# 9xVoice_MikeB_SMD_v1_0c.net
KiCad netlist of a schematic drawn in EAGLE
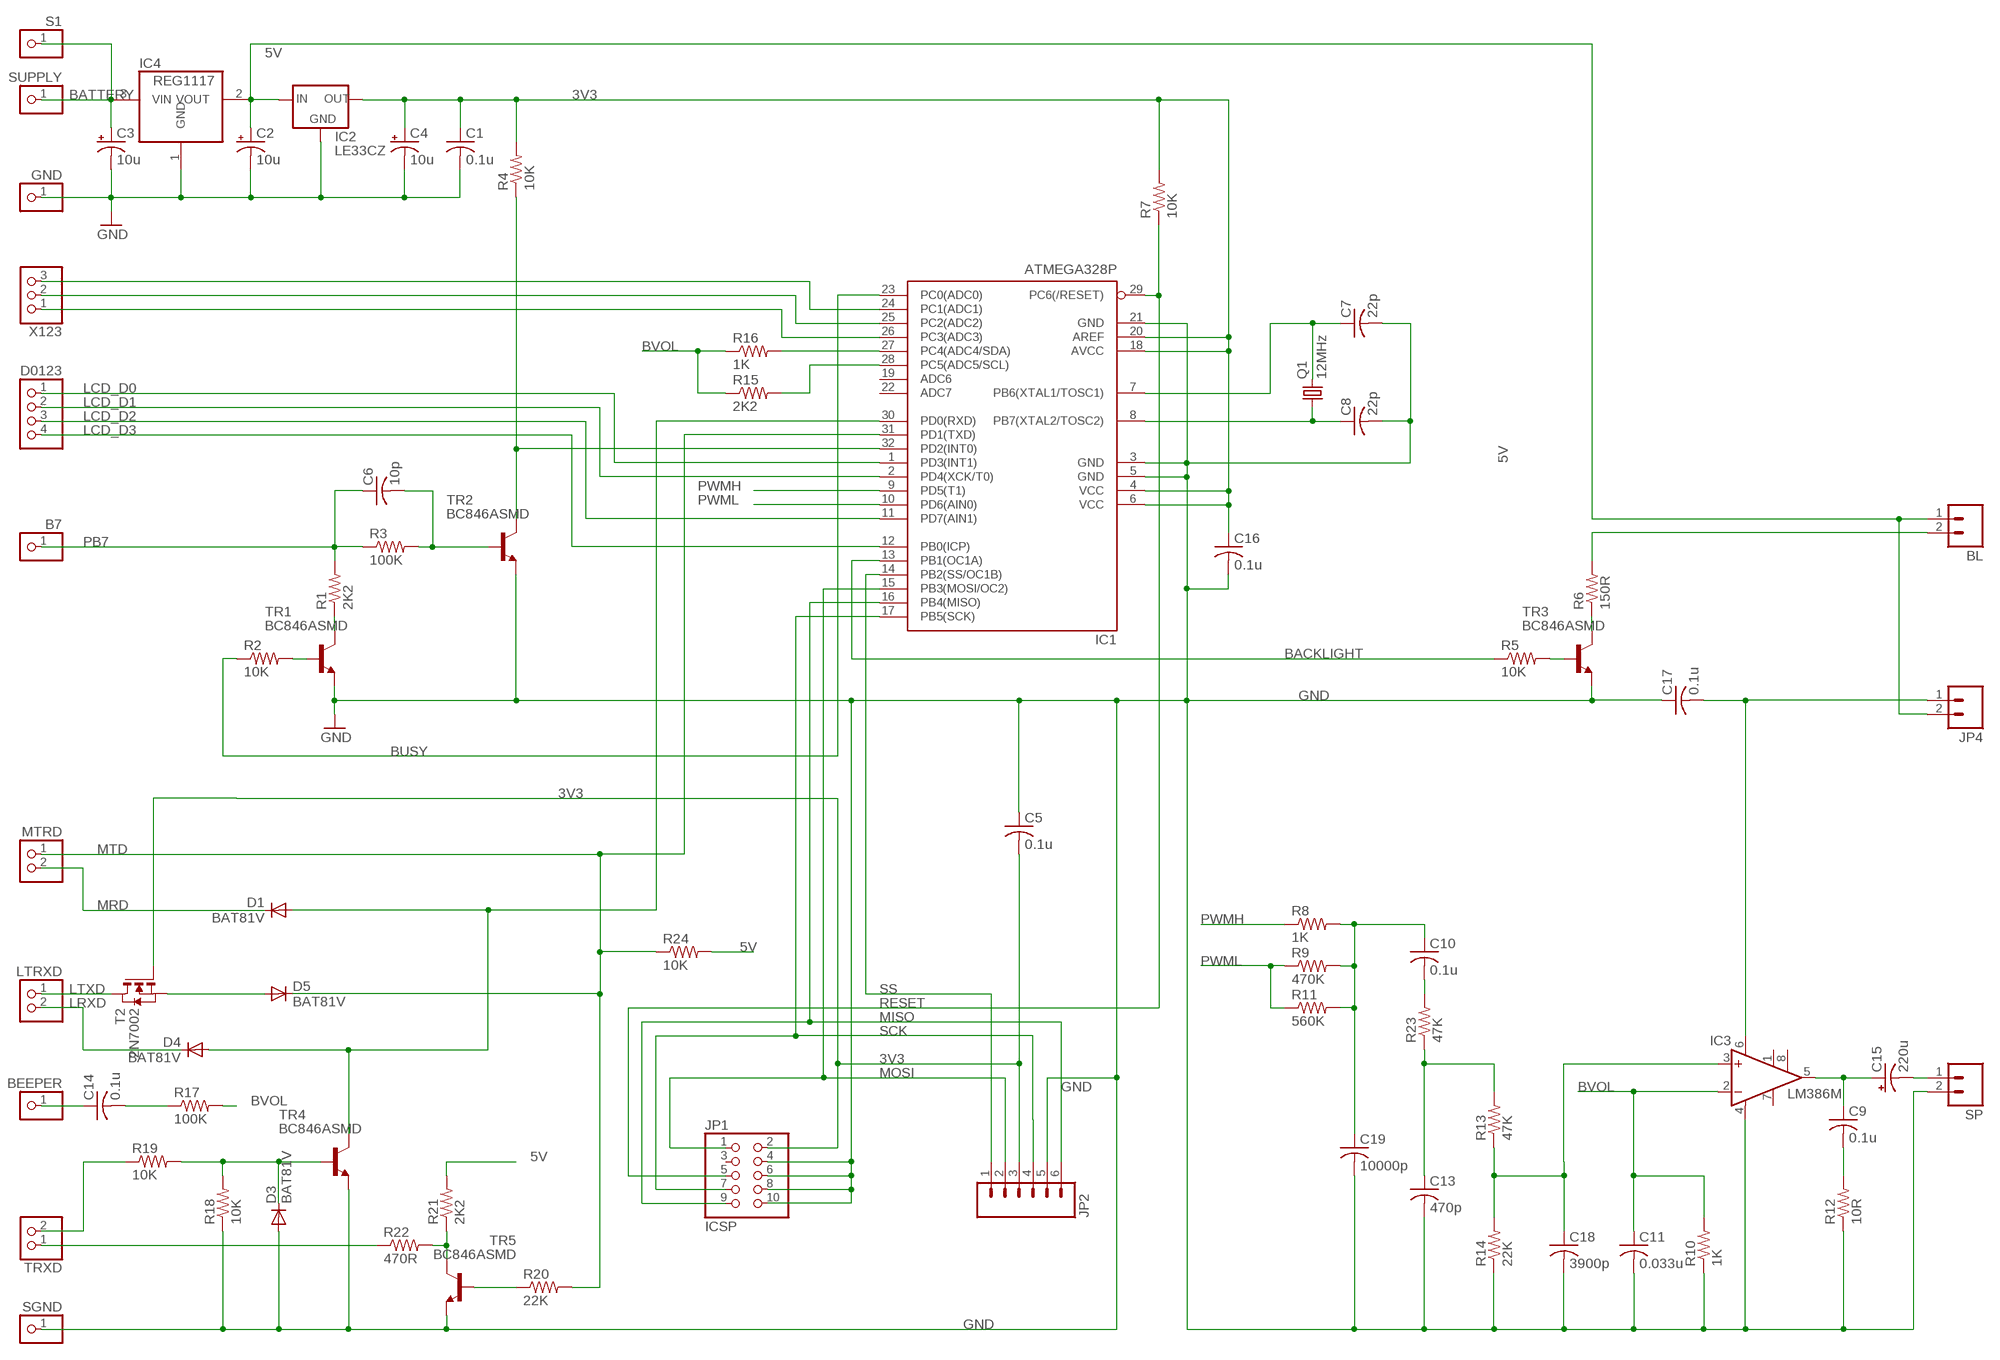
[diagram p0: schematic, sheet 1]

(export (version "E")
  (design (tool "Eeschema 10.0.6"))
  (components
    (comp (ref "B7")
      (value "PINHD-1X1")
      (footprint "eagle-import:1X01")
      (libsource (lib "eagle-import") (part "PINHD-1X1"))
    )
    (comp (ref "BEEPER")
      (value "PINHD-1X1")
      (footprint "eagle-import:1X01")
      (libsource (lib "eagle-import") (part "PINHD-1X1"))
    )
    (comp (ref "BL")
      (value "M02PTH")
      (footprint "eagle-import:1X02")
      (libsource (lib "eagle-import") (part "M02PTH"))
    )
    (comp (ref "C1")
      (value "0.1u")
      (footprint "eagle-import:C1206")
      (libsource (lib "eagle-import") (part "C-USC1206"))
    )
    (comp (ref "C2")
      (value "10u")
      (footprint "eagle-import:A_3216-18R")
      (libsource (lib "eagle-import") (part "CPOL-USA/3216-18R"))
    )
    (comp (ref "C3")
      (value "10u")
      (footprint "eagle-import:A_3216-18R")
      (libsource (lib "eagle-import") (part "CPOL-USA/3216-18R"))
    )
    (comp (ref "C4")
      (value "10u")
      (footprint "eagle-import:A_3216-18R")
      (libsource (lib "eagle-import") (part "CPOL-USA/3216-18R"))
    )
    (comp (ref "C5")
      (value "0.1u")
      (footprint "eagle-import:C1206")
      (libsource (lib "eagle-import") (part "C-USC1206"))
    )
    (comp (ref "C6")
      (value "10p")
      (footprint "eagle-import:C1206")
      (libsource (lib "eagle-import") (part "C-USC1206"))
    )
    (comp (ref "C7")
      (value "22p")
      (footprint "eagle-import:C1206")
      (libsource (lib "eagle-import") (part "C-USC1206"))
    )
    (comp (ref "C8")
      (value "22p")
      (footprint "eagle-import:C1206")
      (libsource (lib "eagle-import") (part "C-USC1206"))
    )
    (comp (ref "C9")
      (value "0.1u")
      (footprint "eagle-import:C1206")
      (libsource (lib "eagle-import") (part "C-USC1206"))
    )
    (comp (ref "C10")
      (value "0.1u")
      (footprint "eagle-import:C1206")
      (libsource (lib "eagle-import") (part "C-USC1206"))
    )
    (comp (ref "C11")
      (value "0.033u")
      (footprint "eagle-import:C1206")
      (libsource (lib "eagle-import") (part "C-USC1206"))
    )
    (comp (ref "C13")
      (value "470p")
      (footprint "eagle-import:C1206")
      (libsource (lib "eagle-import") (part "C-USC1206"))
    )
    (comp (ref "C14")
      (value "0.1u")
      (footprint "eagle-import:C1206")
      (libsource (lib "eagle-import") (part "C-USC1206"))
    )
    (comp (ref "C15")
      (value "220u")
      (footprint "eagle-import:CT7343")
      (libsource (lib "eagle-import") (part "CPOL-USCT7343"))
    )
    (comp (ref "C16")
      (value "0.1u")
      (footprint "eagle-import:C1206")
      (libsource (lib "eagle-import") (part "C-USC1206"))
    )
    (comp (ref "C17")
      (value "0.1u")
      (footprint "eagle-import:C1206")
      (libsource (lib "eagle-import") (part "C-USC1206"))
    )
    (comp (ref "C18")
      (value "3900p")
      (footprint "eagle-import:C1206")
      (libsource (lib "eagle-import") (part "C-USC1206"))
    )
    (comp (ref "C19")
      (value "10000p")
      (footprint "eagle-import:C1206")
      (libsource (lib "eagle-import") (part "C-USC1206"))
    )
    (comp (ref "D1")
      (value "BAT81V")
      (footprint "eagle-import:SOD123")
      (libsource (lib "eagle-import") (part "DIODE-SOD123"))
    )
    (comp (ref "D3")
      (value "BAT81V")
      (footprint "eagle-import:SOD123")
      (libsource (lib "eagle-import") (part "DIODE-SOD123"))
    )
    (comp (ref "D4")
      (value "BAT81V")
      (footprint "eagle-import:SOD123")
      (libsource (lib "eagle-import") (part "DIODE-SOD123"))
    )
    (comp (ref "D5")
      (value "BAT81V")
      (footprint "eagle-import:SOD123")
      (libsource (lib "eagle-import") (part "DIODE-SOD123"))
    )
    (comp (ref "D0123")
      (value "PINHD-1X4")
      (footprint "eagle-import:1X04")
      (libsource (lib "eagle-import") (part "PINHD-1X4"))
    )
    (comp (ref "GND")
      (value "PINHD-1X1")
      (footprint "eagle-import:1X01")
      (libsource (lib "eagle-import") (part "PINHD-1X1"))
    )
    (comp (ref "IC1")
      (value "ATMEGA328P")
      (footprint "eagle-import:TQFP32-08")
      (fields
        (field (name "MPN") "ATMEGA8-16AU")
        (field (name "MPN_1") "ATMEGA8-16AU")
        (field (name "OC_FARNELL") "9171371")
        (field (name "OC_NEWARK") "73M8863")
      )
      (libsource (lib "eagle-import") (part "MEGA8-AI"))
    )
    (comp (ref "IC2")
      (value "LE33CZ")
      (footprint "eagle-import:SOT23")
      (libsource (lib "eagle-import") (part "XC63FPM"))
    )
    (comp (ref "IC3")
      (value "LM386M")
      (footprint "eagle-import:SO08")
      (libsource (lib "eagle-import") (part "LM386?-M1"))
    )
    (comp (ref "IC4")
      (value "REG1117")
      (footprint "eagle-import:SOT223")
      (libsource (lib "eagle-import") (part "REG1117"))
    )
    (comp (ref "JP1")
      (value "ICSP")
      (footprint "eagle-import:2X05")
      (libsource (lib "eagle-import") (part "PINHD-2X5"))
    )
    (comp (ref "JP2")
      (value "M06SIP")
      (footprint "eagle-import:1X06")
      (libsource (lib "eagle-import") (part "M06SIP"))
    )
    (comp (ref "JP4")
      (value "M02PTH")
      (footprint "eagle-import:1X02")
      (libsource (lib "eagle-import") (part "M02PTH"))
    )
    (comp (ref "LTRXD")
      (value "PINHD-1X2")
      (footprint "eagle-import:1X02")
      (libsource (lib "eagle-import") (part "PINHD-1X2"))
    )
    (comp (ref "MTRD")
      (value "PINHD-1X2")
      (footprint "eagle-import:1X02")
      (libsource (lib "eagle-import") (part "PINHD-1X2"))
    )
    (comp (ref "Q1")
      (value "12MHz")
      (footprint "eagle-import:2-SMD")
      (libsource (lib "eagle-import") (part "7A"))
    )
    (comp (ref "R1")
      (value "2K2")
      (footprint "eagle-import:R1206")
      (libsource (lib "eagle-import") (part "R-US_R1206"))
    )
    (comp (ref "R2")
      (value "10K")
      (footprint "eagle-import:R1206")
      (libsource (lib "eagle-import") (part "R-US_R1206"))
    )
    (comp (ref "R3")
      (value "100K")
      (footprint "eagle-import:R1206")
      (libsource (lib "eagle-import") (part "R-US_R1206"))
    )
    (comp (ref "R4")
      (value "10K")
      (footprint "eagle-import:R1206")
      (libsource (lib "eagle-import") (part "R-US_R1206"))
    )
    (comp (ref "R5")
      (value "10K")
      (footprint "eagle-import:R1206")
      (libsource (lib "eagle-import") (part "R-US_R1206"))
    )
    (comp (ref "R6")
      (value "150R")
      (footprint "eagle-import:R1206")
      (libsource (lib "eagle-import") (part "R-US_R1206"))
    )
    (comp (ref "R7")
      (value "10K")
      (footprint "eagle-import:R1206")
      (libsource (lib "eagle-import") (part "R-US_R1206"))
    )
    (comp (ref "R8")
      (value "1K")
      (footprint "eagle-import:R1206")
      (libsource (lib "eagle-import") (part "R-US_R1206"))
    )
    (comp (ref "R9")
      (value "470K")
      (footprint "eagle-import:R1206")
      (libsource (lib "eagle-import") (part "R-US_R1206"))
    )
    (comp (ref "R10")
      (value "1K")
      (footprint "eagle-import:R1206")
      (libsource (lib "eagle-import") (part "R-US_R1206"))
    )
    (comp (ref "R11")
      (value "560K")
      (footprint "eagle-import:R1206")
      (libsource (lib "eagle-import") (part "R-US_R1206"))
    )
    (comp (ref "R12")
      (value "10R")
      (footprint "eagle-import:R1206")
      (libsource (lib "eagle-import") (part "R-US_R1206"))
    )
    (comp (ref "R13")
      (value "47K")
      (footprint "eagle-import:R1206")
      (libsource (lib "eagle-import") (part "R-US_R1206"))
    )
    (comp (ref "R14")
      (value "22K")
      (footprint "eagle-import:R1206")
      (libsource (lib "eagle-import") (part "R-US_R1206"))
    )
    (comp (ref "R15")
      (value "2K2")
      (footprint "eagle-import:R1206")
      (libsource (lib "eagle-import") (part "R-US_R1206"))
    )
    (comp (ref "R16")
      (value "1K")
      (footprint "eagle-import:R1206")
      (libsource (lib "eagle-import") (part "R-US_R1206"))
    )
    (comp (ref "R17")
      (value "100K")
      (footprint "eagle-import:R1206")
      (libsource (lib "eagle-import") (part "R-US_R1206"))
    )
    (comp (ref "R18")
      (value "10K")
      (footprint "eagle-import:R1206")
      (libsource (lib "eagle-import") (part "R-US_R1206"))
    )
    (comp (ref "R19")
      (value "10K")
      (footprint "eagle-import:R1206")
      (libsource (lib "eagle-import") (part "R-US_R1206"))
    )
    (comp (ref "R20")
      (value "22K")
      (footprint "eagle-import:R1206")
      (libsource (lib "eagle-import") (part "R-US_R1206"))
    )
    (comp (ref "R21")
      (value "2K2")
      (footprint "eagle-import:R1206")
      (libsource (lib "eagle-import") (part "R-US_R1206"))
    )
    (comp (ref "R22")
      (value "470R")
      (footprint "eagle-import:R1206")
      (libsource (lib "eagle-import") (part "R-US_R1206"))
    )
    (comp (ref "R23")
      (value "47K")
      (footprint "eagle-import:R1206")
      (libsource (lib "eagle-import") (part "R-US_R1206"))
    )
    (comp (ref "R24")
      (value "10K")
      (footprint "eagle-import:R1206")
      (libsource (lib "eagle-import") (part "R-US_R1206"))
    )
    (comp (ref "S1")
      (value "PINHD-1X1")
      (footprint "eagle-import:1X01")
      (libsource (lib "eagle-import") (part "PINHD-1X1"))
    )
    (comp (ref "SGND")
      (value "PINHD-1X1")
      (footprint "eagle-import:1X01")
      (libsource (lib "eagle-import") (part "PINHD-1X1"))
    )
    (comp (ref "SP")
      (value "M02PTH")
      (footprint "eagle-import:1X02")
      (libsource (lib "eagle-import") (part "M02PTH"))
    )
    (comp (ref "SUPPLY")
      (value "PINHD-1X1")
      (footprint "eagle-import:1X01")
      (libsource (lib "eagle-import") (part "PINHD-1X1"))
    )
    (comp (ref "T2")
      (value "2N7002")
      (footprint "eagle-import:SOT-23")
      (libsource (lib "eagle-import") (part "NMOSSOT23"))
    )
    (comp (ref "TR1")
      (value "BC846ASMD")
      (footprint "eagle-import:SOT23")
      (libsource (lib "eagle-import") (part "BC846SMDA"))
    )
    (comp (ref "TR2")
      (value "BC846ASMD")
      (footprint "eagle-import:SOT23")
      (libsource (lib "eagle-import") (part "BC846SMDA"))
    )
    (comp (ref "TR3")
      (value "BC846ASMD")
      (footprint "eagle-import:SOT23")
      (libsource (lib "eagle-import") (part "BC846SMDA"))
    )
    (comp (ref "TR4")
      (value "BC846ASMD")
      (footprint "eagle-import:SOT23")
      (libsource (lib "eagle-import") (part "BC846SMDA"))
    )
    (comp (ref "TR5")
      (value "BC846ASMD")
      (footprint "eagle-import:SOT23")
      (libsource (lib "eagle-import") (part "transistor-npn_BC846SMDA"))
    )
    (comp (ref "TRXD")
      (value "PINHD-1X2")
      (footprint "eagle-import:1X02")
      (libsource (lib "eagle-import") (part "PINHD-1X2"))
    )
    (comp (ref "X123")
      (value "PINHD-1X3")
      (footprint "eagle-import:1X03")
      (libsource (lib "eagle-import") (part "PINHD-1X3"))
    )
  )
  (nets
    (net (code "1") (name "/3V3") (class "Default")
      (node (ref "C1") (pin "1") (pinfunction "1_1") (pintype "passive"))
      (node (ref "C16") (pin "1") (pinfunction "1_1") (pintype "passive"))
      (node (ref "C4") (pin "+") (pinfunction "+_+") (pintype "passive"))
      (node (ref "C5") (pin "2") (pinfunction "2_2") (pintype "passive"))
      (node (ref "IC1") (pin "18") (pinfunction "AVCC_18") (pintype "power_in"))
      (node (ref "IC1") (pin "20") (pinfunction "AREF_20") (pintype "passive"))
      (node (ref "IC1") (pin "4") (pinfunction "VCC_4") (pintype "power_in"))
      (node (ref "IC1") (pin "6") (pinfunction "VCC_6") (pintype "power_in"))
      (node (ref "IC2") (pin "2") (pinfunction "OUT_2") (pintype "passive"))
      (node (ref "JP1") (pin "2") (pinfunction "2_2") (pintype "passive"))
      (node (ref "JP2") (pin "3") (pinfunction "3_3") (pintype "passive"))
      (node (ref "R4") (pin "2") (pinfunction "2_2") (pintype "passive"))
      (node (ref "R7") (pin "2") (pinfunction "2_2") (pintype "passive"))
      (node (ref "T2") (pin "3") (pinfunction "G_3") (pintype "passive"))
    )
    (net (code "2") (name "/5V") (class "Default")
      (node (ref "BL") (pin "1") (pinfunction "1_1") (pintype "passive"))
      (node (ref "C2") (pin "+") (pinfunction "+_+") (pintype "passive"))
      (node (ref "IC2") (pin "3") (pinfunction "IN_3") (pintype "input"))
      (node (ref "IC4") (pin "2") (pinfunction "VOUT_2") (pintype "output"))
      (node (ref "JP4") (pin "2") (pinfunction "2_2") (pintype "passive"))
      (node (ref "R21") (pin "2") (pinfunction "2_2") (pintype "passive"))
      (node (ref "R24") (pin "2") (pinfunction "2_2") (pintype "passive"))
    )
    (net (code "3") (name "/BACKLIGHT") (class "Default")
      (node (ref "IC1") (pin "13") (pinfunction "PB1(OC1A)_13") (pintype "bidirectional"))
      (node (ref "R5") (pin "1") (pinfunction "1_1") (pintype "passive"))
    )
    (net (code "4") (name "/BATTERY") (class "Default")
      (node (ref "C3") (pin "+") (pinfunction "+_+") (pintype "passive"))
      (node (ref "IC4") (pin "3") (pinfunction "VIN_3") (pintype "input"))
      (node (ref "S1") (pin "1") (pinfunction "1_1") (pintype "passive"))
      (node (ref "SUPPLY") (pin "1") (pinfunction "1_1") (pintype "passive"))
    )
    (net (code "5") (name "/BUSY") (class "Default")
      (node (ref "IC1") (pin "23") (pinfunction "PC0(ADC0)_23") (pintype "bidirectional"))
      (node (ref "R2") (pin "1") (pinfunction "1_1") (pintype "passive"))
    )
    (net (code "6") (name "/BVOL") (class "Default")
      (node (ref "C11") (pin "1") (pinfunction "1_1") (pintype "passive"))
      (node (ref "IC3") (pin "2") (pinfunction "-IN_2") (pintype "input"))
      (node (ref "R10") (pin "2") (pinfunction "2_2") (pintype "passive"))
      (node (ref "R15") (pin "1") (pinfunction "1_1") (pintype "passive"))
      (node (ref "R16") (pin "1") (pinfunction "1_1") (pintype "passive"))
      (node (ref "R17") (pin "2") (pinfunction "2_2") (pintype "passive"))
    )
    (net (code "7") (name "/LCD_D0") (class "Default")
      (node (ref "D0123") (pin "1") (pinfunction "1_1") (pintype "passive"))
      (node (ref "IC1") (pin "1") (pinfunction "PD3(INT1)_1") (pintype "bidirectional"))
    )
    (net (code "8") (name "/LCD_D1") (class "Default")
      (node (ref "D0123") (pin "2") (pinfunction "2_2") (pintype "passive"))
      (node (ref "IC1") (pin "2") (pinfunction "PD4(XCK/T0)_2") (pintype "bidirectional"))
    )
    (net (code "9") (name "/LCD_D2") (class "Default")
      (node (ref "D0123") (pin "3") (pinfunction "3_3") (pintype "passive"))
      (node (ref "IC1") (pin "11") (pinfunction "PD7(AIN1)_11") (pintype "bidirectional"))
    )
    (net (code "10") (name "/LCD_D3") (class "Default")
      (node (ref "D0123") (pin "4") (pinfunction "4_4") (pintype "passive"))
      (node (ref "IC1") (pin "12") (pinfunction "PB0(ICP)_12") (pintype "bidirectional"))
    )
    (net (code "11") (name "/LRXD") (class "Default")
      (node (ref "D4") (pin "C") (pinfunction "C_C") (pintype "passive"))
      (node (ref "LTRXD") (pin "2") (pinfunction "2_2") (pintype "passive"))
    )
    (net (code "12") (name "/LTXD") (class "Default")
      (node (ref "LTRXD") (pin "1") (pinfunction "1_1") (pintype "passive"))
      (node (ref "T2") (pin "1") (pinfunction "D_1") (pintype "passive"))
    )
    (net (code "13") (name "/MISO") (class "Default")
      (node (ref "IC1") (pin "16") (pinfunction "PB4(MISO)_16") (pintype "bidirectional"))
      (node (ref "JP1") (pin "9") (pinfunction "9_9") (pintype "passive"))
      (node (ref "JP2") (pin "6") (pinfunction "6_6") (pintype "passive"))
    )
    (net (code "14") (name "/MOSI") (class "Default")
      (node (ref "IC1") (pin "15") (pinfunction "PB3(MOSI/OC2)_15") (pintype "bidirectional"))
      (node (ref "JP1") (pin "1") (pinfunction "1_1") (pintype "passive"))
      (node (ref "JP2") (pin "2") (pinfunction "2_2") (pintype "passive"))
    )
    (net (code "15") (name "/MRD") (class "Default")
      (node (ref "D1") (pin "C") (pinfunction "C_C") (pintype "passive"))
      (node (ref "MTRD") (pin "2") (pinfunction "2_2") (pintype "passive"))
    )
    (net (code "16") (name "/MTD") (class "Default")
      (node (ref "D5") (pin "C") (pinfunction "C_C") (pintype "passive"))
      (node (ref "IC1") (pin "31") (pinfunction "PD1(TXD)_31") (pintype "bidirectional"))
      (node (ref "MTRD") (pin "1") (pinfunction "1_1") (pintype "passive"))
      (node (ref "R20") (pin "2") (pinfunction "2_2") (pintype "passive"))
      (node (ref "R24") (pin "1") (pinfunction "1_1") (pintype "passive"))
    )
    (net (code "17") (name "/PB7") (class "Default")
      (node (ref "B7") (pin "1") (pinfunction "1_1") (pintype "passive"))
      (node (ref "C6") (pin "1") (pinfunction "1_1") (pintype "passive"))
      (node (ref "R1") (pin "2") (pinfunction "2_2") (pintype "passive"))
      (node (ref "R3") (pin "1") (pinfunction "1_1") (pintype "passive"))
    )
    (net (code "18") (name "/PWMH") (class "Default")
      (node (ref "IC1") (pin "9") (pinfunction "PD5(T1)_9") (pintype "bidirectional"))
      (node (ref "R8") (pin "1") (pinfunction "1_1") (pintype "passive"))
    )
    (net (code "19") (name "/PWML") (class "Default")
      (node (ref "IC1") (pin "10") (pinfunction "PD6(AIN0)_10") (pintype "bidirectional"))
      (node (ref "R11") (pin "1") (pinfunction "1_1") (pintype "passive"))
      (node (ref "R9") (pin "1") (pinfunction "1_1") (pintype "passive"))
    )
    (net (code "20") (name "/RESET") (class "Default")
      (node (ref "IC1") (pin "29") (pinfunction "PC6(/RESET)_29") (pintype "bidirectional"))
      (node (ref "JP1") (pin "5") (pinfunction "5_5") (pintype "passive"))
      (node (ref "R7") (pin "1") (pinfunction "1_1") (pintype "passive"))
    )
    (net (code "21") (name "/SCK") (class "Default")
      (node (ref "IC1") (pin "17") (pinfunction "PB5(SCK)_17") (pintype "bidirectional"))
      (node (ref "JP1") (pin "7") (pinfunction "7_7") (pintype "passive"))
      (node (ref "JP2") (pin "4") (pinfunction "4_4") (pintype "passive"))
    )
    (net (code "22") (name "/SS") (class "Default")
      (node (ref "IC1") (pin "14") (pinfunction "PB2(SS/OC1B)_14") (pintype "bidirectional"))
      (node (ref "JP2") (pin "1") (pinfunction "1_1") (pintype "passive"))
    )
    (net (code "23") (name "GND") (class "Default")
      (node (ref "C1") (pin "2") (pinfunction "2_2") (pintype "passive"))
      (node (ref "C11") (pin "2") (pinfunction "2_2") (pintype "passive"))
      (node (ref "C13") (pin "2") (pinfunction "2_2") (pintype "passive"))
      (node (ref "C16") (pin "2") (pinfunction "2_2") (pintype "passive"))
      (node (ref "C17") (pin "1") (pinfunction "1_1") (pintype "passive"))
      (node (ref "C18") (pin "2") (pinfunction "2_2") (pintype "passive"))
      (node (ref "C19") (pin "2") (pinfunction "2_2") (pintype "passive"))
      (node (ref "C2") (pin "-") (pinfunction "-_-") (pintype "passive"))
      (node (ref "C3") (pin "-") (pinfunction "-_-") (pintype "passive"))
      (node (ref "C4") (pin "-") (pinfunction "-_-") (pintype "passive"))
      (node (ref "C5") (pin "1") (pinfunction "1_1") (pintype "passive"))
      (node (ref "C7") (pin "2") (pinfunction "2_2") (pintype "passive"))
      (node (ref "C8") (pin "2") (pinfunction "2_2") (pintype "passive"))
      (node (ref "D3") (pin "A") (pinfunction "A_A") (pintype "passive"))
      (node (ref "GND") (pin "1") (pinfunction "1_1") (pintype "passive"))
      (node (ref "IC1") (pin "21") (pinfunction "GND_21") (pintype "power_in"))
      (node (ref "IC1") (pin "3") (pinfunction "GND_3") (pintype "power_in"))
      (node (ref "IC1") (pin "5") (pinfunction "GND_5") (pintype "power_in"))
      (node (ref "IC2") (pin "1") (pinfunction "GND_1") (pintype "input"))
      (node (ref "IC3") (pin "4") (pinfunction "GND_4") (pintype "power_in"))
      (node (ref "IC4") (pin "1") (pinfunction "GND_1") (pintype "power_in"))
      (node (ref "JP1") (pin "10") (pinfunction "10_10") (pintype "passive"))
      (node (ref "JP1") (pin "4") (pinfunction "4_4") (pintype "passive"))
      (node (ref "JP1") (pin "6") (pinfunction "6_6") (pintype "passive"))
      (node (ref "JP1") (pin "8") (pinfunction "8_8") (pintype "passive"))
      (node (ref "JP2") (pin "5") (pinfunction "5_5") (pintype "passive"))
      (node (ref "R10") (pin "1") (pinfunction "1_1") (pintype "passive"))
      (node (ref "R12") (pin "1") (pinfunction "1_1") (pintype "passive"))
      (node (ref "R14") (pin "1") (pinfunction "1_1") (pintype "passive"))
      (node (ref "R18") (pin "1") (pinfunction "1_1") (pintype "passive"))
      (node (ref "SGND") (pin "1") (pinfunction "1_1") (pintype "passive"))
      (node (ref "SP") (pin "2") (pinfunction "2_2") (pintype "passive"))
      (node (ref "TR1") (pin "2") (pinfunction "E_2") (pintype "passive"))
      (node (ref "TR2") (pin "2") (pinfunction "E_2") (pintype "passive"))
      (node (ref "TR3") (pin "2") (pinfunction "E_2") (pintype "passive"))
      (node (ref "TR4") (pin "2") (pinfunction "E_2") (pintype "passive"))
      (node (ref "TR5") (pin "2") (pinfunction "E_2") (pintype "passive"))
    )
    (net (code "24") (name "Net-(BEEPER-Pad1)") (class "Default")
      (node (ref "BEEPER") (pin "1") (pinfunction "1_1") (pintype "passive"))
      (node (ref "C14") (pin "1") (pinfunction "1_1") (pintype "passive"))
    )
    (net (code "25") (name "Net-(BL-Pad2)") (class "Default")
      (node (ref "BL") (pin "2") (pinfunction "2_2") (pintype "passive"))
      (node (ref "R6") (pin "2") (pinfunction "2_2") (pintype "passive"))
    )
    (net (code "26") (name "Net-(C9-Pad2)") (class "Default")
      (node (ref "C9") (pin "2") (pinfunction "2_2") (pintype "passive"))
      (node (ref "R12") (pin "2") (pinfunction "2_2") (pintype "passive"))
    )
    (net (code "27") (name "Net-(C10-Pad1)") (class "Default")
      (node (ref "C10") (pin "1") (pinfunction "1_1") (pintype "passive"))
      (node (ref "C19") (pin "1") (pinfunction "1_1") (pintype "passive"))
      (node (ref "R11") (pin "2") (pinfunction "2_2") (pintype "passive"))
      (node (ref "R8") (pin "2") (pinfunction "2_2") (pintype "passive"))
      (node (ref "R9") (pin "2") (pinfunction "2_2") (pintype "passive"))
    )
    (net (code "28") (name "Net-(C10-Pad2)") (class "Default")
      (node (ref "C10") (pin "2") (pinfunction "2_2") (pintype "passive"))
      (node (ref "R23") (pin "2") (pinfunction "2_2") (pintype "passive"))
    )
    (net (code "29") (name "Net-(C13-Pad1)") (class "Default")
      (node (ref "C13") (pin "1") (pinfunction "1_1") (pintype "passive"))
      (node (ref "R13") (pin "2") (pinfunction "2_2") (pintype "passive"))
      (node (ref "R23") (pin "1") (pinfunction "1_1") (pintype "passive"))
    )
    (net (code "30") (name "Net-(C14-Pad2)") (class "Default")
      (node (ref "C14") (pin "2") (pinfunction "2_2") (pintype "passive"))
      (node (ref "R17") (pin "1") (pinfunction "1_1") (pintype "passive"))
    )
    (net (code "31") (name "Net-(C15-Pad-)") (class "Default")
      (node (ref "C15") (pin "-") (pinfunction "-_-") (pintype "passive"))
      (node (ref "SP") (pin "1") (pinfunction "1_1") (pintype "passive"))
    )
    (net (code "32") (name "Net-(IC1-PB6(XTAL1{slash}TOSC1))") (class "Default")
      (node (ref "C7") (pin "1") (pinfunction "1_1") (pintype "passive"))
      (node (ref "IC1") (pin "7") (pinfunction "PB6(XTAL1/TOSC1)_7") (pintype "bidirectional"))
      (node (ref "Q1") (pin "P$2") (pinfunction "2_P$2") (pintype "passive"))
    )
    (net (code "33") (name "Net-(IC1-PB7(XTAL2{slash}TOSC2))") (class "Default")
      (node (ref "C8") (pin "1") (pinfunction "1_1") (pintype "passive"))
      (node (ref "IC1") (pin "8") (pinfunction "PB7(XTAL2/TOSC2)_8") (pintype "bidirectional"))
      (node (ref "Q1") (pin "P$1") (pinfunction "1_P$1") (pintype "passive"))
    )
    (net (code "34") (name "Net-(IC1-PC1(ADC1))") (class "Default")
      (node (ref "IC1") (pin "24") (pinfunction "PC1(ADC1)_24") (pintype "bidirectional"))
      (node (ref "X123") (pin "3") (pinfunction "3_3") (pintype "passive"))
    )
    (net (code "35") (name "Net-(IC1-PC2(ADC2))") (class "Default")
      (node (ref "IC1") (pin "25") (pinfunction "PC2(ADC2)_25") (pintype "bidirectional"))
      (node (ref "X123") (pin "2") (pinfunction "2_2") (pintype "passive"))
    )
    (net (code "36") (name "Net-(IC1-PC3(ADC3))") (class "Default")
      (node (ref "IC1") (pin "26") (pinfunction "PC3(ADC3)_26") (pintype "bidirectional"))
      (node (ref "X123") (pin "1") (pinfunction "1_1") (pintype "passive"))
    )
    (net (code "37") (name "Net-(IC1-PC4(ADC4{slash}SDA))") (class "Default")
      (node (ref "IC1") (pin "27") (pinfunction "PC4(ADC4/SDA)_27") (pintype "bidirectional"))
      (node (ref "R16") (pin "2") (pinfunction "2_2") (pintype "passive"))
    )
    (net (code "38") (name "Net-(IC1-PC5(ADC5{slash}SCL))") (class "Default")
      (node (ref "IC1") (pin "28") (pinfunction "PC5(ADC5/SCL)_28") (pintype "bidirectional"))
      (node (ref "R15") (pin "2") (pinfunction "2_2") (pintype "passive"))
    )
    (net (code "39") (name "Net-(IC1-PD0(RXD))") (class "Default")
      (node (ref "D1") (pin "A") (pinfunction "A_A") (pintype "passive"))
      (node (ref "D4") (pin "A") (pinfunction "A_A") (pintype "passive"))
      (node (ref "IC1") (pin "30") (pinfunction "PD0(RXD)_30") (pintype "bidirectional"))
      (node (ref "TR4") (pin "3") (pinfunction "C_3") (pintype "passive"))
    )
    (net (code "40") (name "Net-(IC1-PD2(INT0))") (class "Default")
      (node (ref "IC1") (pin "32") (pinfunction "PD2(INT0)_32") (pintype "bidirectional"))
      (node (ref "R4") (pin "1") (pinfunction "1_1") (pintype "passive"))
      (node (ref "TR2") (pin "3") (pinfunction "C_3") (pintype "passive"))
    )
    (net (code "41") (name "Net-(IC3-+IN)") (class "Default")
      (node (ref "C18") (pin "1") (pinfunction "1_1") (pintype "passive"))
      (node (ref "IC3") (pin "3") (pinfunction "+IN_3") (pintype "input"))
      (node (ref "R13") (pin "1") (pinfunction "1_1") (pintype "passive"))
      (node (ref "R14") (pin "2") (pinfunction "2_2") (pintype "passive"))
    )
    (net (code "42") (name "Net-(IC3-OUT)") (class "Default")
      (node (ref "C15") (pin "+") (pinfunction "+_+") (pintype "passive"))
      (node (ref "C9") (pin "1") (pinfunction "1_1") (pintype "passive"))
      (node (ref "IC3") (pin "5") (pinfunction "OUT_5") (pintype "output"))
    )
    (net (code "43") (name "Net-(IC3-VS)") (class "Default")
      (node (ref "C17") (pin "2") (pinfunction "2_2") (pintype "passive"))
      (node (ref "IC3") (pin "6") (pinfunction "VS_6") (pintype "power_in"))
      (node (ref "JP4") (pin "1") (pinfunction "1_1") (pintype "passive"))
    )
    (net (code "44") (name "Net-(R19-Pad1)") (class "Default")
      (node (ref "R19") (pin "1") (pinfunction "1_1") (pintype "passive"))
      (node (ref "TRXD") (pin "2") (pinfunction "2_2") (pintype "passive"))
    )
    (net (code "45") (name "Net-(R22-Pad1)") (class "Default")
      (node (ref "R22") (pin "1") (pinfunction "1_1") (pintype "passive"))
      (node (ref "TRXD") (pin "1") (pinfunction "1_1") (pintype "passive"))
    )
    (net (code "46") (name "Net-(T2-S)") (class "Default")
      (node (ref "D5") (pin "A") (pinfunction "A_A") (pintype "passive"))
      (node (ref "T2") (pin "2") (pinfunction "S_2") (pintype "passive"))
    )
    (net (code "47") (name "Net-(TR1-B)") (class "Default")
      (node (ref "R2") (pin "2") (pinfunction "2_2") (pintype "passive"))
      (node (ref "TR1") (pin "1") (pinfunction "B_1") (pintype "passive"))
    )
    (net (code "48") (name "Net-(TR1-C)") (class "Default")
      (node (ref "R1") (pin "1") (pinfunction "1_1") (pintype "passive"))
      (node (ref "TR1") (pin "3") (pinfunction "C_3") (pintype "passive"))
    )
    (net (code "49") (name "Net-(TR2-B)") (class "Default")
      (node (ref "C6") (pin "2") (pinfunction "2_2") (pintype "passive"))
      (node (ref "R3") (pin "2") (pinfunction "2_2") (pintype "passive"))
      (node (ref "TR2") (pin "1") (pinfunction "B_1") (pintype "passive"))
    )
    (net (code "50") (name "Net-(TR3-B)") (class "Default")
      (node (ref "R5") (pin "2") (pinfunction "2_2") (pintype "passive"))
      (node (ref "TR3") (pin "1") (pinfunction "B_1") (pintype "passive"))
    )
    (net (code "51") (name "Net-(TR3-C)") (class "Default")
      (node (ref "R6") (pin "1") (pinfunction "1_1") (pintype "passive"))
      (node (ref "TR3") (pin "3") (pinfunction "C_3") (pintype "passive"))
    )
    (net (code "52") (name "Net-(TR4-B)") (class "Default")
      (node (ref "D3") (pin "C") (pinfunction "C_C") (pintype "passive"))
      (node (ref "R18") (pin "2") (pinfunction "2_2") (pintype "passive"))
      (node (ref "R19") (pin "2") (pinfunction "2_2") (pintype "passive"))
      (node (ref "TR4") (pin "1") (pinfunction "B_1") (pintype "passive"))
    )
    (net (code "53") (name "Net-(TR5-B)") (class "Default")
      (node (ref "R20") (pin "1") (pinfunction "1_1") (pintype "passive"))
      (node (ref "TR5") (pin "1") (pinfunction "B_1") (pintype "passive"))
    )
    (net (code "54") (name "Net-(TR5-C)") (class "Default")
      (node (ref "R21") (pin "1") (pinfunction "1_1") (pintype "passive"))
      (node (ref "R22") (pin "2") (pinfunction "2_2") (pintype "passive"))
      (node (ref "TR5") (pin "3") (pinfunction "C_3") (pintype "passive"))
    )
    (net (code "55") (name "unconnected-(IC1-ADC6-Pad19)") (class "Default")
      (node (ref "IC1") (pin "19") (pinfunction "ADC6_19") (pintype "bidirectional"))
    )
    (net (code "56") (name "unconnected-(IC1-ADC7-Pad22)") (class "Default")
      (node (ref "IC1") (pin "22") (pinfunction "ADC7_22") (pintype "bidirectional"))
    )
    (net (code "57") (name "unconnected-(IC3-BYPASS-Pad7)") (class "Default")
      (node (ref "IC3") (pin "7") (pinfunction "BYPASS_7") (pintype "passive"))
    )
    (net (code "58") (name "unconnected-(IC3-GAIN-Pad1)") (class "Default")
      (node (ref "IC3") (pin "1") (pinfunction "GAIN_1") (pintype "passive"))
    )
    (net (code "59") (name "unconnected-(IC3-GAIN-Pad8)") (class "Default")
      (node (ref "IC3") (pin "8") (pinfunction "GAIN_8") (pintype "passive"))
    )
    (net (code "60") (name "unconnected-(JP1-Pad3)") (class "Default")
      (node (ref "JP1") (pin "3") (pinfunction "3_3") (pintype "passive"))
    )
  )
)
